# CS1238-24-Bit-ADC.net
KiCad netlist of a schematic drawn in Altium Designer
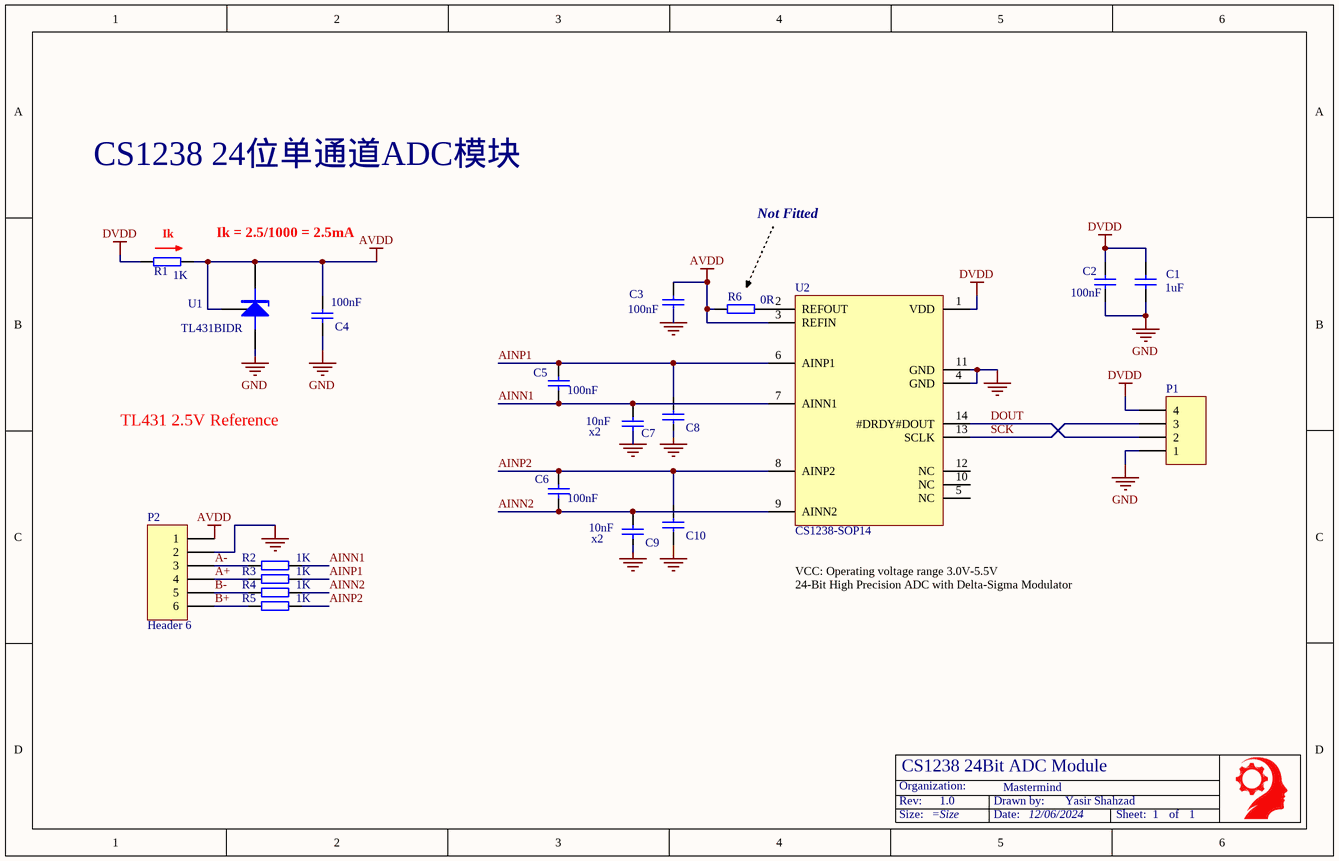
[diagram p0: CS1238-24-Bit-ADC.SchDoc]

(export (version "E")
  (design (tool "Eeschema 10.0.6"))
  (components
    (comp (ref "*")
      (value "TitleBlock")
      (description "Title Block for Schematic Sheets")
      (libsource (lib "Mastermind Devices") (part "TitleBlock"))
    )
    (comp (ref "C1")
      (value "1uF")
      (footprint "C0603")
      (description "Capacitor, X5R, ±10%, 6.3V")
      (fields
        (field (name "PART NUMBER") "C0603-N.C.")
        (field (name "MANUFACTURER") "N.A.")
        (field (name "PUBLISHER") "Nordic Semiconductor")
      )
      (libsource (lib "Mastermind Devices") (part "Cap_0603"))
    )
    (comp (ref "C2")
      (value "100nF")
      (footprint "C0603")
      (description "Capacitor, X5R, ±10%, 6.3V")
      (fields
        (field (name "PART NUMBER") "C0603-N.C.")
        (field (name "MANUFACTURER") "N.A.")
        (field (name "PUBLISHER") "Nordic Semiconductor")
      )
      (libsource (lib "Mastermind Devices") (part "Cap_0603"))
    )
    (comp (ref "C3")
      (value "100nF")
      (footprint "C0603")
      (description "Capacitor, X5R, ±10%, 6.3V")
      (fields
        (field (name "PART NUMBER") "C0603-N.C.")
        (field (name "MANUFACTURER") "N.A.")
        (field (name "PUBLISHER") "Nordic Semiconductor")
      )
      (libsource (lib "Mastermind Devices") (part "Cap_0603"))
    )
    (comp (ref "C4")
      (value "100nF")
      (footprint "C0603")
      (description "Capacitor, X5R, ±10%, 6.3V")
      (fields
        (field (name "PART NUMBER") "C0603-N.C.")
        (field (name "MANUFACTURER") "N.A.")
        (field (name "PUBLISHER") "Nordic Semiconductor")
      )
      (libsource (lib "Mastermind Devices") (part "Cap_0603"))
    )
    (comp (ref "C5")
      (value "100nF")
      (footprint "C0603")
      (description "Capacitor, X5R, ±10%, 6.3V")
      (fields
        (field (name "PART NUMBER") "C0603-N.C.")
        (field (name "MANUFACTURER") "N.A.")
        (field (name "PUBLISHER") "Nordic Semiconductor")
      )
      (libsource (lib "Mastermind Devices") (part "Cap_0603"))
    )
    (comp (ref "C6")
      (value "100nF")
      (footprint "C0603")
      (description "Capacitor, X5R, ±10%, 6.3V")
      (fields
        (field (name "PART NUMBER") "C0603-N.C.")
        (field (name "MANUFACTURER") "N.A.")
        (field (name "PUBLISHER") "Nordic Semiconductor")
      )
      (libsource (lib "Mastermind Devices") (part "Cap_0603"))
    )
    (comp (ref "C7")
      (value "10nF")
      (footprint "C0603")
      (description "Capacitor, X5R, ±10%, 6.3V")
      (fields
        (field (name "PART NUMBER") "C0603-N.C.")
        (field (name "MANUFACTURER") "N.A.")
        (field (name "PUBLISHER") "Nordic Semiconductor")
      )
      (libsource (lib "Mastermind Devices") (part "Cap_0603"))
    )
    (comp (ref "C8")
      (value "10nF")
      (footprint "C0603")
      (description "Capacitor, X5R, ±10%, 6.3V")
      (fields
        (field (name "PART NUMBER") "C0603-N.C.")
        (field (name "MANUFACTURER") "N.A.")
        (field (name "PUBLISHER") "Nordic Semiconductor")
      )
      (libsource (lib "Mastermind Devices") (part "Cap_0603"))
    )
    (comp (ref "C9")
      (value "10nF")
      (footprint "C0603")
      (description "Capacitor, X5R, ±10%, 6.3V")
      (fields
        (field (name "PART NUMBER") "C0603-N.C.")
        (field (name "MANUFACTURER") "N.A.")
        (field (name "PUBLISHER") "Nordic Semiconductor")
      )
      (libsource (lib "Mastermind Devices") (part "Cap_0603"))
    )
    (comp (ref "C10")
      (value "10nF")
      (footprint "C0603")
      (description "Capacitor, X5R, ±10%, 6.3V")
      (fields
        (field (name "PART NUMBER") "C0603-N.C.")
        (field (name "MANUFACTURER") "N.A.")
        (field (name "PUBLISHER") "Nordic Semiconductor")
      )
      (libsource (lib "Mastermind Devices") (part "Cap_0603"))
    )
    (comp (ref "P1")
      (value "~")
      (footprint "HDR1X4")
      (description "Header, 4-Pin")
      (fields (field (name "PUBLISHER") "Altium Limited"))
      (libsource (lib "Mastermind Devices") (part "Header 4"))
    )
    (comp (ref "P2")
      (value "Header 6")
      (footprint "HDR1X6")
      (description "Header, 6-Pin")
      (fields (field (name "PUBLISHER") "Altium Limited"))
      (libsource (lib "Mastermind Connectors") (part "Header 6"))
    )
    (comp (ref "R1")
      (value "1kΩ")
      (footprint "R0603")
      (description "Resistor, ±1%, 0.100W")
      (fields
        (field (name "PART NUMBER") "R0603-N.C.Ω")
        (field (name "MANUFACTURER") "N.A.")
        (field (name "PUBLISHER") "Nordic Semiconductor")
      )
      (libsource (lib "Mastermind Devices") (part "Res_0603"))
    )
    (comp (ref "R2")
      (value "1kΩ")
      (footprint "R0603")
      (description "Resistor, ±1%, 0.100W")
      (fields
        (field (name "PART NUMBER") "R0603-N.C.Ω")
        (field (name "MANUFACTURER") "N.A.")
        (field (name "PUBLISHER") "Nordic Semiconductor")
      )
      (libsource (lib "Mastermind Devices") (part "Res_0603"))
    )
    (comp (ref "R3")
      (value "1kΩ")
      (footprint "R0603")
      (description "Resistor, ±1%, 0.100W")
      (fields
        (field (name "PART NUMBER") "R0603-N.C.Ω")
        (field (name "MANUFACTURER") "N.A.")
        (field (name "PUBLISHER") "Nordic Semiconductor")
      )
      (libsource (lib "Mastermind Devices") (part "Res_0603"))
    )
    (comp (ref "R4")
      (value "1kΩ")
      (footprint "R0603")
      (description "Resistor, ±1%, 0.100W")
      (fields
        (field (name "PART NUMBER") "R0603-N.C.Ω")
        (field (name "MANUFACTURER") "N.A.")
        (field (name "PUBLISHER") "Nordic Semiconductor")
      )
      (libsource (lib "Mastermind Devices") (part "Res_0603"))
    )
    (comp (ref "R5")
      (value "1kΩ")
      (footprint "R0603")
      (description "Resistor, ±1%, 0.100W")
      (fields
        (field (name "PART NUMBER") "R0603-N.C.Ω")
        (field (name "MANUFACTURER") "N.A.")
        (field (name "PUBLISHER") "Nordic Semiconductor")
      )
      (libsource (lib "Mastermind Devices") (part "Res_0603"))
    )
    (comp (ref "R6")
      (value "0Ω")
      (footprint "R0603")
      (description "Resistor, ±1%, 0.100W")
      (fields
        (field (name "PART NUMBER") "R0603-N.C.Ω")
        (field (name "MANUFACTURER") "N.A.")
        (field (name "PUBLISHER") "Nordic Semiconductor")
      )
      (libsource (lib "") (part "Res_0603_1"))
    )
    (comp (ref "U1")
      (value "TL431BIDR")
      (footprint "SOIC-8E")
      (description "TL431, TL432 Precision Programmable Reference")
      (fields (field (name "MANUFACTURER") "TI(德州仪器)") (field (name "TOLERANCE") "±0.5%"))
      (libsource (lib "Mastermind Devices") (part "TL431BIDR"))
    )
    (comp (ref "U2")
      (value "CS1238-SOP14")
      (footprint "SOP-14_L8.6-W3.9-P1.27-LS6.0-BL")
      (fields (field (name "MANUFACTURER") "CHIPSEA(芯海科技)"))
      (libsource (lib "Mastermind Devices") (part "CS1238-SOP14"))
    )
  )
  (nets
    (net (code "1") (name "/A+") (class "Default")
      (node (ref "P2") (pin "4") (pinfunction "4_4") (pintype "passive"))
      (node (ref "R3") (pin "2") (pinfunction "2_2") (pintype "passive"))
    )
    (net (code "2") (name "/A-") (class "Default")
      (node (ref "P2") (pin "3") (pinfunction "3_3") (pintype "passive"))
      (node (ref "R2") (pin "2") (pinfunction "2_2") (pintype "passive"))
    )
    (net (code "3") (name "/AINN1") (class "Default")
      (node (ref "C5") (pin "1") (pinfunction "1_1") (pintype "passive"))
      (node (ref "C7") (pin "2") (pinfunction "2_2") (pintype "passive"))
      (node (ref "R2") (pin "1") (pinfunction "1_1") (pintype "passive"))
      (node (ref "U2") (pin "7") (pinfunction "AINN1_7") (pintype "passive"))
    )
    (net (code "4") (name "/AINN2") (class "Default")
      (node (ref "C6") (pin "2") (pinfunction "2_2") (pintype "passive"))
      (node (ref "C9") (pin "2") (pinfunction "2_2") (pintype "passive"))
      (node (ref "R4") (pin "1") (pinfunction "1_1") (pintype "passive"))
      (node (ref "U2") (pin "9") (pinfunction "AINN2_9") (pintype "passive"))
    )
    (net (code "5") (name "/AINP1") (class "Default")
      (node (ref "C5") (pin "2") (pinfunction "2_2") (pintype "passive"))
      (node (ref "C8") (pin "1") (pinfunction "1_1") (pintype "passive"))
      (node (ref "R3") (pin "1") (pinfunction "1_1") (pintype "passive"))
      (node (ref "U2") (pin "6") (pinfunction "AINP1_6") (pintype "passive"))
    )
    (net (code "6") (name "/AINP2") (class "Default")
      (node (ref "C10") (pin "2") (pinfunction "2_2") (pintype "passive"))
      (node (ref "C6") (pin "1") (pinfunction "1_1") (pintype "passive"))
      (node (ref "R5") (pin "1") (pinfunction "1_1") (pintype "passive"))
      (node (ref "U2") (pin "8") (pinfunction "AINP2_8") (pintype "passive"))
    )
    (net (code "7") (name "/B+") (class "Default")
      (node (ref "P2") (pin "6") (pinfunction "6_6") (pintype "passive"))
      (node (ref "R5") (pin "2") (pinfunction "2_2") (pintype "passive"))
    )
    (net (code "8") (name "/B-") (class "Default")
      (node (ref "P2") (pin "5") (pinfunction "5_5") (pintype "passive"))
      (node (ref "R4") (pin "2") (pinfunction "2_2") (pintype "passive"))
    )
    (net (code "9") (name "/DOUT") (class "Default")
      (node (ref "P1") (pin "2") (pinfunction "2_2") (pintype "passive"))
      (node (ref "U2") (pin "14") (pinfunction "#DRDY#DOUT_14") (pintype "passive"))
    )
    (net (code "10") (name "/SCK") (class "Default")
      (node (ref "P1") (pin "3") (pinfunction "3_3") (pintype "passive"))
      (node (ref "U2") (pin "13") (pinfunction "SCLK_13") (pintype "passive"))
    )
    (net (code "11") (name "AVDD") (class "Default")
      (node (ref "C3") (pin "1") (pinfunction "1_1") (pintype "passive"))
      (node (ref "C4") (pin "1") (pinfunction "1_1") (pintype "passive"))
      (node (ref "P2") (pin "1") (pinfunction "1_1") (pintype "passive"))
      (node (ref "R1") (pin "1") (pinfunction "1_1") (pintype "passive"))
      (node (ref "R6") (pin "1") (pinfunction "1_1") (pintype "passive"))
      (node (ref "U1") (pin "1") (pinfunction "K_1") (pintype "passive"))
      (node (ref "U1") (pin "8") (pinfunction "Ref_8") (pintype "passive"))
      (node (ref "U2") (pin "3") (pinfunction "REFIN_3") (pintype "passive"))
    )
    (net (code "12") (name "DVDD") (class "Default")
      (node (ref "C1") (pin "1") (pinfunction "1_1") (pintype "passive"))
      (node (ref "C2") (pin "1") (pinfunction "1_1") (pintype "passive"))
      (node (ref "P1") (pin "4") (pinfunction "4_4") (pintype "passive"))
      (node (ref "R1") (pin "2") (pinfunction "2_2") (pintype "passive"))
      (node (ref "U2") (pin "1") (pinfunction "VDD_1") (pintype "passive"))
    )
    (net (code "13") (name "GND") (class "Default")
      (node (ref "C1") (pin "2") (pinfunction "2_2") (pintype "passive"))
      (node (ref "C10") (pin "1") (pinfunction "1_1") (pintype "passive"))
      (node (ref "C2") (pin "2") (pinfunction "2_2") (pintype "passive"))
      (node (ref "C3") (pin "2") (pinfunction "2_2") (pintype "passive"))
      (node (ref "C4") (pin "2") (pinfunction "2_2") (pintype "passive"))
      (node (ref "C7") (pin "1") (pinfunction "1_1") (pintype "passive"))
      (node (ref "C8") (pin "2") (pinfunction "2_2") (pintype "passive"))
      (node (ref "C9") (pin "1") (pinfunction "1_1") (pintype "passive"))
      (node (ref "P1") (pin "1") (pinfunction "1_1") (pintype "passive"))
      (node (ref "P2") (pin "2") (pinfunction "2_2") (pintype "passive"))
      (node (ref "U1") (pin "3") (pinfunction "A_3") (pintype "passive"))
      (node (ref "U2") (pin "11") (pinfunction "GND_11") (pintype "passive"))
      (node (ref "U2") (pin "4") (pinfunction "GND_4") (pintype "passive"))
    )
    (net (code "14") (name "Net-(U2-REFOUT)") (class "Default")
      (node (ref "R6") (pin "2") (pinfunction "2_2") (pintype "passive"))
      (node (ref "U2") (pin "2") (pinfunction "REFOUT_2") (pintype "passive"))
    )
    (net (code "15") (name "unconnected-(U1-NC-Pad4)") (class "Default")
      (node (ref "U1") (pin "4") (pinfunction "NC_4") (pintype "passive"))
    )
    (net (code "16") (name "unconnected-(U1-NC-Pad5)") (class "Default")
      (node (ref "U1") (pin "5") (pinfunction "NC_5") (pintype "passive"))
    )
    (net (code "17") (name "unconnected-(U2-NC-Pad5)") (class "Default")
      (node (ref "U2") (pin "5") (pinfunction "NC_5") (pintype "passive"))
    )
    (net (code "18") (name "unconnected-(U2-NC-Pad10)") (class "Default")
      (node (ref "U2") (pin "10") (pinfunction "NC_10") (pintype "passive"))
    )
    (net (code "19") (name "unconnected-(U2-NC-Pad12)") (class "Default")
      (node (ref "U2") (pin "12") (pinfunction "NC_12") (pintype "passive"))
    )
  )
)
